# SCH_arduinomotor_2024-02-12.net
KiCad netlist of a schematic drawn in EasyEDA
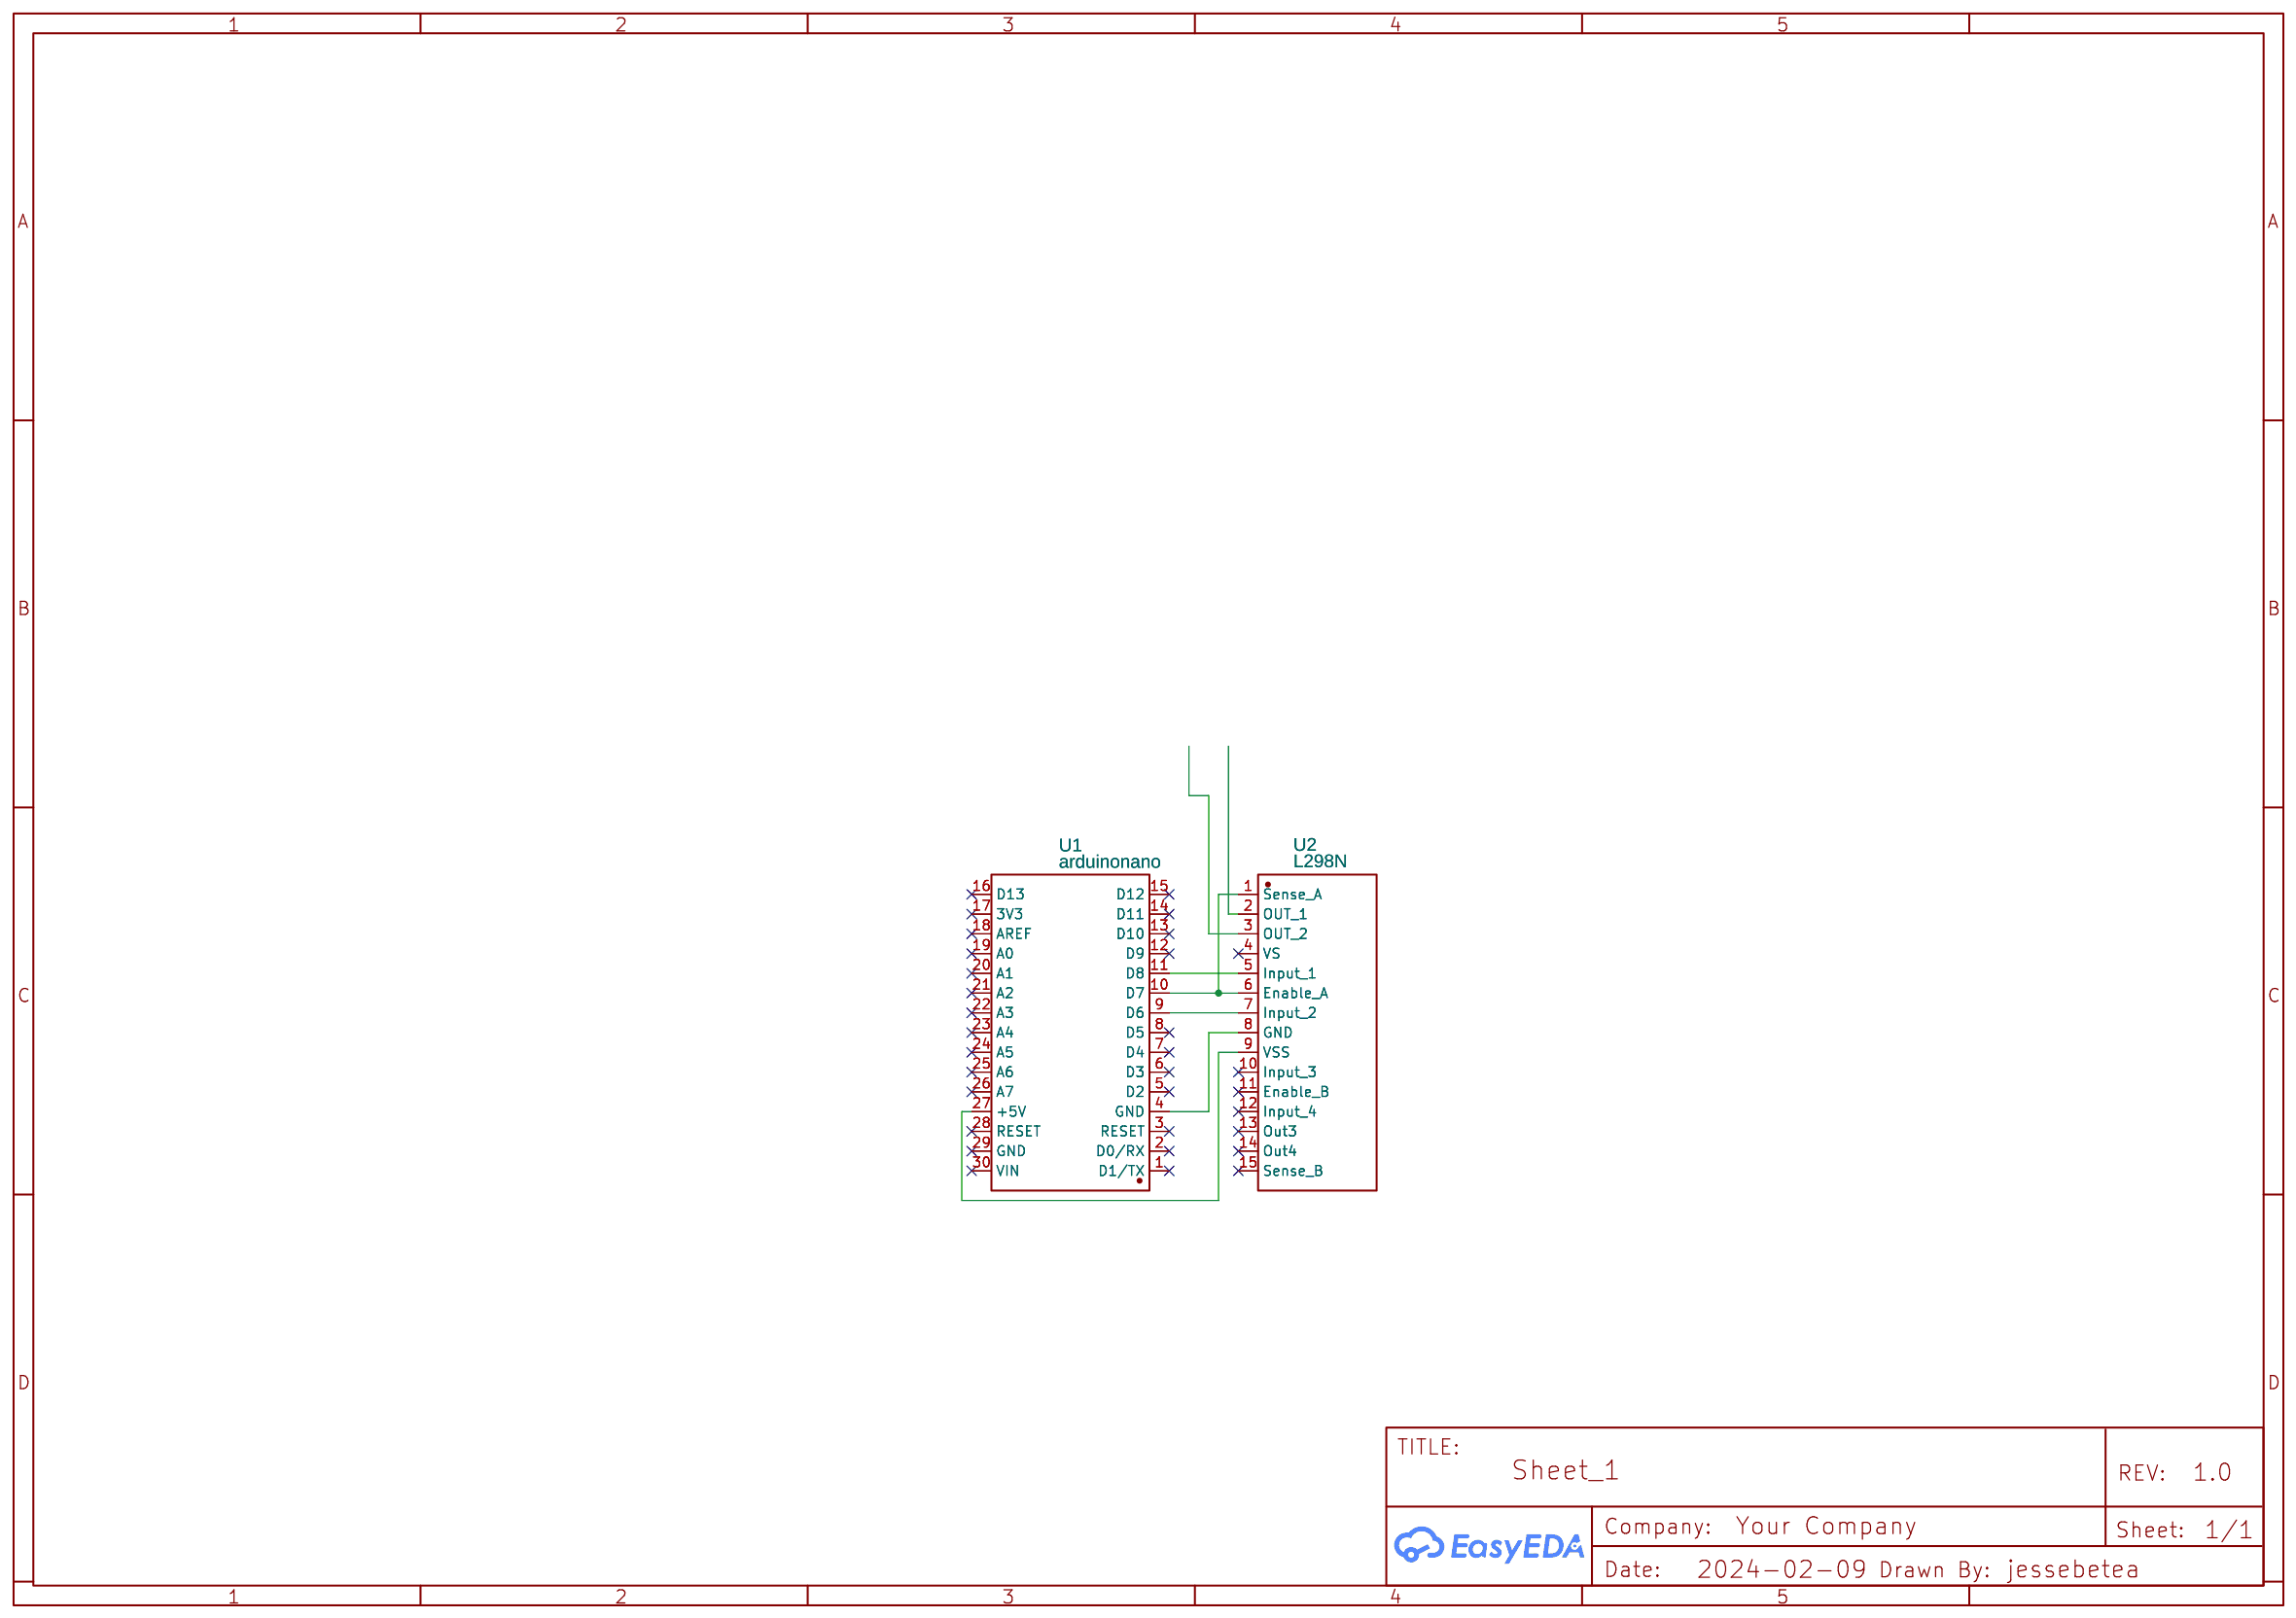
[diagram p0: schematic sheet]

(export (version "E")
  (design (tool "Eeschema 10.0.6"))
  (components
    (comp (ref "U1")
      (value "arduinonano")
      (fields (field (name "Manufacturer Part") "ARDUINO_NANO"))
      (libsource (lib "") (part "ARDUINO_NANO"))
    )
    (comp (ref "U2")
      (value "L298N")
      (fields (field (name "Manufacturer") "HGSEMI(华冠)"))
      (libsource (lib "") (part "L298N"))
    )
  )
  (nets
    (net (code "1") (name "Net-(U1-+5V)") (class "Default")
      (node (ref "U1") (pin "27") (pinfunction "+5V_27") (pintype "unspecified"))
      (node (ref "U2") (pin "9") (pinfunction "VSS_9") (pintype "unspecified"))
    )
    (net (code "2") (name "Net-(U1-D6)") (class "Default")
      (node (ref "U1") (pin "9") (pinfunction "D6_9") (pintype "unspecified"))
      (node (ref "U2") (pin "7") (pinfunction "Input_2_7") (pintype "unspecified"))
    )
    (net (code "3") (name "Net-(U1-D7)") (class "Default")
      (node (ref "U1") (pin "10") (pinfunction "D7_10") (pintype "unspecified"))
      (node (ref "U2") (pin "1") (pinfunction "Sense_A_1") (pintype "unspecified"))
      (node (ref "U2") (pin "6") (pinfunction "Enable_A_6") (pintype "unspecified"))
    )
    (net (code "4") (name "Net-(U1-D8)") (class "Default")
      (node (ref "U1") (pin "11") (pinfunction "D8_11") (pintype "unspecified"))
      (node (ref "U2") (pin "5") (pinfunction "Input_1_5") (pintype "unspecified"))
    )
    (net (code "5") (name "Net-(U2-GND)") (class "Default")
      (node (ref "U1") (pin "4") (pinfunction "GND_4") (pintype "unspecified"))
      (node (ref "U2") (pin "8") (pinfunction "GND_8") (pintype "unspecified"))
    )
    (net (code "6") (name "unconnected-(U1-3V3-Pad17)") (class "Default")
      (node (ref "U1") (pin "17") (pinfunction "3V3_17") (pintype "unspecified+no_connect"))
    )
    (net (code "7") (name "unconnected-(U1-A0-Pad19)") (class "Default")
      (node (ref "U1") (pin "19") (pinfunction "A0_19") (pintype "unspecified+no_connect"))
    )
    (net (code "8") (name "unconnected-(U1-A1-Pad20)") (class "Default")
      (node (ref "U1") (pin "20") (pinfunction "A1_20") (pintype "unspecified+no_connect"))
    )
    (net (code "9") (name "unconnected-(U1-A2-Pad21)") (class "Default")
      (node (ref "U1") (pin "21") (pinfunction "A2_21") (pintype "unspecified+no_connect"))
    )
    (net (code "10") (name "unconnected-(U1-A3-Pad22)") (class "Default")
      (node (ref "U1") (pin "22") (pinfunction "A3_22") (pintype "unspecified+no_connect"))
    )
    (net (code "11") (name "unconnected-(U1-A4-Pad23)") (class "Default")
      (node (ref "U1") (pin "23") (pinfunction "A4_23") (pintype "unspecified+no_connect"))
    )
    (net (code "12") (name "unconnected-(U1-A5-Pad24)") (class "Default")
      (node (ref "U1") (pin "24") (pinfunction "A5_24") (pintype "unspecified+no_connect"))
    )
    (net (code "13") (name "unconnected-(U1-A6-Pad25)") (class "Default")
      (node (ref "U1") (pin "25") (pinfunction "A6_25") (pintype "unspecified+no_connect"))
    )
    (net (code "14") (name "unconnected-(U1-A7-Pad26)") (class "Default")
      (node (ref "U1") (pin "26") (pinfunction "A7_26") (pintype "unspecified+no_connect"))
    )
    (net (code "15") (name "unconnected-(U1-AREF-Pad18)") (class "Default")
      (node (ref "U1") (pin "18") (pinfunction "AREF_18") (pintype "unspecified+no_connect"))
    )
    (net (code "16") (name "unconnected-(U1-D0{slash}RX-Pad2)") (class "Default")
      (node (ref "U1") (pin "2") (pinfunction "D0/RX_2") (pintype "unspecified+no_connect"))
    )
    (net (code "17") (name "unconnected-(U1-D1{slash}TX-Pad1)") (class "Default")
      (node (ref "U1") (pin "1") (pinfunction "D1/TX_1") (pintype "unspecified+no_connect"))
    )
    (net (code "18") (name "unconnected-(U1-D2-Pad5)") (class "Default")
      (node (ref "U1") (pin "5") (pinfunction "D2_5") (pintype "unspecified+no_connect"))
    )
    (net (code "19") (name "unconnected-(U1-D3-Pad6)") (class "Default")
      (node (ref "U1") (pin "6") (pinfunction "D3_6") (pintype "unspecified+no_connect"))
    )
    (net (code "20") (name "unconnected-(U1-D4-Pad7)") (class "Default")
      (node (ref "U1") (pin "7") (pinfunction "D4_7") (pintype "unspecified+no_connect"))
    )
    (net (code "21") (name "unconnected-(U1-D5-Pad8)") (class "Default")
      (node (ref "U1") (pin "8") (pinfunction "D5_8") (pintype "unspecified+no_connect"))
    )
    (net (code "22") (name "unconnected-(U1-D9-Pad12)") (class "Default")
      (node (ref "U1") (pin "12") (pinfunction "D9_12") (pintype "unspecified+no_connect"))
    )
    (net (code "23") (name "unconnected-(U1-D10-Pad13)") (class "Default")
      (node (ref "U1") (pin "13") (pinfunction "D10_13") (pintype "unspecified+no_connect"))
    )
    (net (code "24") (name "unconnected-(U1-D11-Pad14)") (class "Default")
      (node (ref "U1") (pin "14") (pinfunction "D11_14") (pintype "unspecified+no_connect"))
    )
    (net (code "25") (name "unconnected-(U1-D12-Pad15)") (class "Default")
      (node (ref "U1") (pin "15") (pinfunction "D12_15") (pintype "unspecified+no_connect"))
    )
    (net (code "26") (name "unconnected-(U1-D13-Pad16)") (class "Default")
      (node (ref "U1") (pin "16") (pinfunction "D13_16") (pintype "unspecified+no_connect"))
    )
    (net (code "27") (name "unconnected-(U1-GND-Pad29)") (class "Default")
      (node (ref "U1") (pin "29") (pinfunction "GND_29") (pintype "unspecified+no_connect"))
    )
    (net (code "28") (name "unconnected-(U1-RESET-Pad3)") (class "Default")
      (node (ref "U1") (pin "3") (pinfunction "RESET_3") (pintype "unspecified+no_connect"))
    )
    (net (code "29") (name "unconnected-(U1-RESET-Pad28)") (class "Default")
      (node (ref "U1") (pin "28") (pinfunction "RESET_28") (pintype "unspecified+no_connect"))
    )
    (net (code "30") (name "unconnected-(U1-VIN-Pad30)") (class "Default")
      (node (ref "U1") (pin "30") (pinfunction "VIN_30") (pintype "unspecified+no_connect"))
    )
    (net (code "31") (name "unconnected-(U2-Enable_B-Pad11)") (class "Default")
      (node (ref "U2") (pin "11") (pinfunction "Enable_B_11") (pintype "unspecified+no_connect"))
    )
    (net (code "32") (name "unconnected-(U2-Input_3-Pad10)") (class "Default")
      (node (ref "U2") (pin "10") (pinfunction "Input_3_10") (pintype "unspecified+no_connect"))
    )
    (net (code "33") (name "unconnected-(U2-Input_4-Pad12)") (class "Default")
      (node (ref "U2") (pin "12") (pinfunction "Input_4_12") (pintype "unspecified+no_connect"))
    )
    (net (code "34") (name "unconnected-(U2-OUT_1-Pad2)") (class "Default")
      (node (ref "U2") (pin "2") (pinfunction "OUT_1_2") (pintype "unspecified"))
    )
    (net (code "35") (name "unconnected-(U2-OUT_2-Pad3)") (class "Default")
      (node (ref "U2") (pin "3") (pinfunction "OUT_2_3") (pintype "unspecified"))
    )
    (net (code "36") (name "unconnected-(U2-Out3-Pad13)") (class "Default")
      (node (ref "U2") (pin "13") (pinfunction "Out3_13") (pintype "unspecified+no_connect"))
    )
    (net (code "37") (name "unconnected-(U2-Out4-Pad14)") (class "Default")
      (node (ref "U2") (pin "14") (pinfunction "Out4_14") (pintype "unspecified+no_connect"))
    )
    (net (code "38") (name "unconnected-(U2-Sense_B-Pad15)") (class "Default")
      (node (ref "U2") (pin "15") (pinfunction "Sense_B_15") (pintype "unspecified+no_connect"))
    )
    (net (code "39") (name "unconnected-(U2-VS-Pad4)") (class "Default")
      (node (ref "U2") (pin "4") (pinfunction "VS_4") (pintype "unspecified+no_connect"))
    )
  )
)
